# Current_Kill.net
KiCad netlist of a schematic drawn in Altium Designer
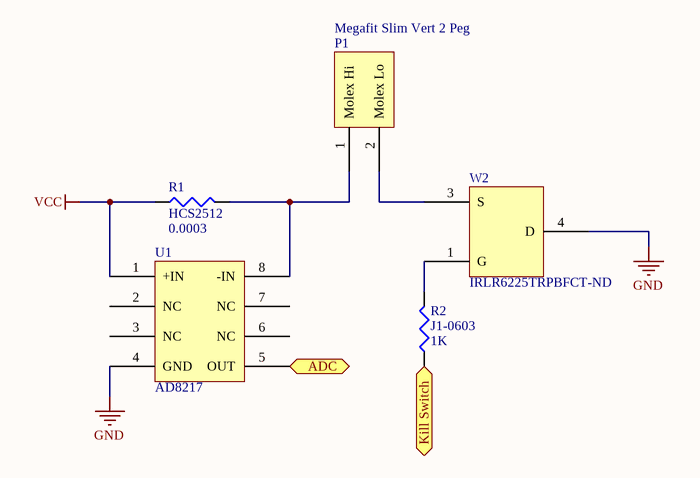
[diagram p0: Current_Kill.SchDoc]

(export (version "E")
  (design (tool "Eeschema 10.0.6"))
  (components
    (comp (ref "P1")
      (value "Megafit Slim Vert 2 Peg")
      (footprint "Molex_DT:76829-0102")
      (fields (field (name "MFGR_PART_NUM") "76829-0102"))
      (libsource (lib "Molex_DT") (part "Megafit Slim Vert 2 Peg"))
    )
    (comp (ref "R1")
      (value "HCS2512")
      (footprint "HCS2512FTL300CT-ND_DT")
      (description "Resistor")
      (fields
        (field (name "ALTIUM_VALUE") "0.0003")
        (field (name "MFGR_PART_NUM") "HCS2512FTL300")
        (field (name "PUBLISHER") "Altium Limited")
      )
      (libsource (lib "Miscellaneous Devices") (part "Res3"))
    )
    (comp (ref "R2")
      (value "J1-0603")
      (footprint "J1-0603")
      (description "Resistor")
      (fields (field (name "ALTIUM_VALUE") "1K") (field (name "PUBLISHER") "Altium Limited"))
      (libsource (lib "Miscellaneous Devices") (part "Res3"))
    )
    (comp (ref "U1")
      (value "AD8217")
      (footprint "AD8217_DT:AD8217_DT")
      (fields (field (name "MFGR_PART_NUM") "AD8217BRMZ-R7"))
      (libsource (lib "AD8217_DT") (part "AD8217"))
    )
    (comp (ref "W2")
      (value "IRLR6225TRPBFCT-ND")
      (footprint "IRLR6225_DT")
      (fields (field (name "MNFR_PART_NUM") "IRLR6225TRPBF"))
      (libsource (lib "IRLR6225_DT") (part "IRLR6225TRPBFCT-ND"))
    )
  )
  (nets
    (net (code "1") (name "/ADC") (class "Default")
      (node (ref "U1") (pin "5") (pinfunction "OUT_5") (pintype "passive"))
    )
    (net (code "2") (name "/Kill Switch") (class "Default")
      (node (ref "R2") (pin "1") (pinfunction "1_1") (pintype "passive"))
    )
    (net (code "3") (name "GND") (class "Default")
      (node (ref "U1") (pin "4") (pinfunction "GND_4") (pintype "passive"))
      (node (ref "W2") (pin "4") (pinfunction "D_4") (pintype "passive"))
    )
    (net (code "4") (name "Net-(P1-Molex_Hi)") (class "Default")
      (node (ref "P1") (pin "1") (pinfunction "Molex_Hi_1") (pintype "passive"))
      (node (ref "R1") (pin "2") (pinfunction "2_2") (pintype "passive"))
      (node (ref "U1") (pin "8") (pinfunction "-IN_8") (pintype "passive"))
    )
    (net (code "5") (name "Net-(P1-Molex_Lo)") (class "Default")
      (node (ref "P1") (pin "2") (pinfunction "Molex_Lo_2") (pintype "passive"))
      (node (ref "W2") (pin "3") (pinfunction "S_3") (pintype "passive"))
    )
    (net (code "6") (name "Net-(W2-G)") (class "Default")
      (node (ref "R2") (pin "2") (pinfunction "2_2") (pintype "passive"))
      (node (ref "W2") (pin "1") (pinfunction "G_1") (pintype "passive"))
    )
    (net (code "7") (name "VCC") (class "Default")
      (node (ref "R1") (pin "1") (pinfunction "1_1") (pintype "passive"))
      (node (ref "U1") (pin "1") (pinfunction "+IN_1") (pintype "passive"))
    )
    (net (code "8") (name "unconnected-(U1-NC-Pad2)") (class "Default")
      (node (ref "U1") (pin "2") (pinfunction "NC_2") (pintype "passive"))
    )
    (net (code "9") (name "unconnected-(U1-NC-Pad3)") (class "Default")
      (node (ref "U1") (pin "3") (pinfunction "NC_3") (pintype "passive"))
    )
    (net (code "10") (name "unconnected-(U1-NC-Pad6)") (class "Default")
      (node (ref "U1") (pin "6") (pinfunction "NC_6") (pintype "passive"))
    )
    (net (code "11") (name "unconnected-(U1-NC-Pad7)") (class "Default")
      (node (ref "U1") (pin "7") (pinfunction "NC_7") (pintype "passive"))
    )
  )
)
